# DC-DC_5V0_To_3V3.net
KiCad netlist of a schematic drawn in Altium Designer
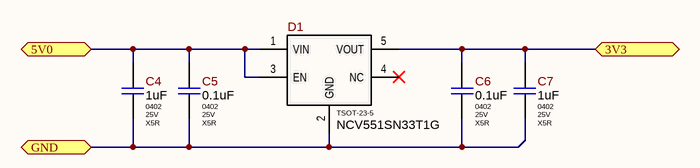
[diagram p0: DC-DC_5V0_To_3V3.SchDoc]

(export (version "E")
  (design (tool "Eeschema 10.0.6"))
  (components
    (comp (ref "C4")
      (value "1uF")
      (footprint "C_CERAMIC_0402_MED")
      (description "1uF 25V Х5R ±10% 0402 Ceramic Capacitor RoHS")
      (fields
        (field (name "PACKAGE") "0402")
        (field (name "VOLTAGE") "25V")
        (field (name "DIELECTRIC TYPE") "X5R")
        (field (name "PART NUMBER") "GRM155R61E105KA12D")
        (field (name "MANUFACTURER") "Murata Electronics")
      )
      (libsource (lib "EL.CVCM.T01") (part "Capacitor-NonPolar"))
    )
    (comp (ref "C5")
      (value "0.1uF")
      (footprint "C_CERAMIC_0402_MED")
      (description "100nF 25V X5R ±10% 0402 Ceramic Capacitor RoHS")
      (fields
        (field (name "PACKAGE") "0402")
        (field (name "VOLTAGE") "25V")
        (field (name "DIELECTRIC TYPE") "X5R")
        (field (name "PART NUMBER") "CL05A104KA5NNNC")
        (field (name "MANUFACTURER") "Samsung Electro-Mechanics")
      )
      (libsource (lib "EL.CVCM.T01") (part "Capacitor-NonPolar"))
    )
    (comp (ref "C6")
      (value "0.1uF")
      (footprint "C_CERAMIC_0402_MED")
      (description "100nF 25V X5R ±10% 0402 Ceramic Capacitor RoHS")
      (fields
        (field (name "PACKAGE") "0402")
        (field (name "VOLTAGE") "25V")
        (field (name "DIELECTRIC TYPE") "X5R")
        (field (name "PART NUMBER") "CL05A104KA5NNNC")
        (field (name "MANUFACTURER") "Samsung Electro-Mechanics")
      )
      (libsource (lib "EL.CVCM.T01") (part "Capacitor-NonPolar"))
    )
    (comp (ref "C7")
      (value "1uF")
      (footprint "C_CERAMIC_0402_MED")
      (description "1uF 25V Х5R ±10% 0402 Ceramic Capacitor RoHS")
      (fields
        (field (name "PACKAGE") "0402")
        (field (name "VOLTAGE") "25V")
        (field (name "DIELECTRIC TYPE") "X5R")
        (field (name "PART NUMBER") "GRM155R61E105KA12D")
        (field (name "MANUFACTURER") "Murata Electronics")
      )
      (libsource (lib "EL.CVCM.T01") (part "Capacitor-NonPolar"))
    )
    (comp (ref "D1")
      (value "NCV551SN33T1G")
      (footprint "TSOT-23-5")
      (description "Fixed 3.3V, 150mA Output, 12V max Input, 4uA Iq, LDO, TSOT-23-5")
      (fields
        (field (name "PACKAGE") "TSOT-23-5")
        (field (name "PART NUMBER") "NCV551SN33T1G")
        (field (name "MANUFACTURER") "Onsemi")
      )
      (libsource (lib "EL.CVCM.T01") (part "NCV551SNxxT1G"))
    )
  )
  (nets
    (net (code "1") (name "/3V3") (class "Default")
      (node (ref "C6") (pin "1") (pinfunction "1_1") (pintype "passive"))
      (node (ref "C7") (pin "1") (pinfunction "1_1") (pintype "passive"))
      (node (ref "D1") (pin "5") (pinfunction "VOUT_5") (pintype "passive"))
    )
    (net (code "2") (name "/5V0") (class "Default")
      (node (ref "C4") (pin "1") (pinfunction "1_1") (pintype "passive"))
      (node (ref "C5") (pin "1") (pinfunction "1_1") (pintype "passive"))
      (node (ref "D1") (pin "1") (pinfunction "VIN_1") (pintype "passive"))
      (node (ref "D1") (pin "3") (pinfunction "EN_3") (pintype "passive"))
    )
    (net (code "3") (name "/GND") (class "Default")
      (node (ref "C4") (pin "2") (pinfunction "2_2") (pintype "passive"))
      (node (ref "C5") (pin "2") (pinfunction "2_2") (pintype "passive"))
      (node (ref "C6") (pin "2") (pinfunction "2_2") (pintype "passive"))
      (node (ref "C7") (pin "2") (pinfunction "2_2") (pintype "passive"))
      (node (ref "D1") (pin "2") (pinfunction "GND_2") (pintype "passive"))
    )
    (net (code "4") (name "unconnected-(D1-NC-Pad4)") (class "Default")
      (node (ref "D1") (pin "4") (pinfunction "NC_4") (pintype "passive+no_connect"))
    )
  )
)
